# RFID_bmd200.net
KiCad netlist of a schematic drawn in EAGLE
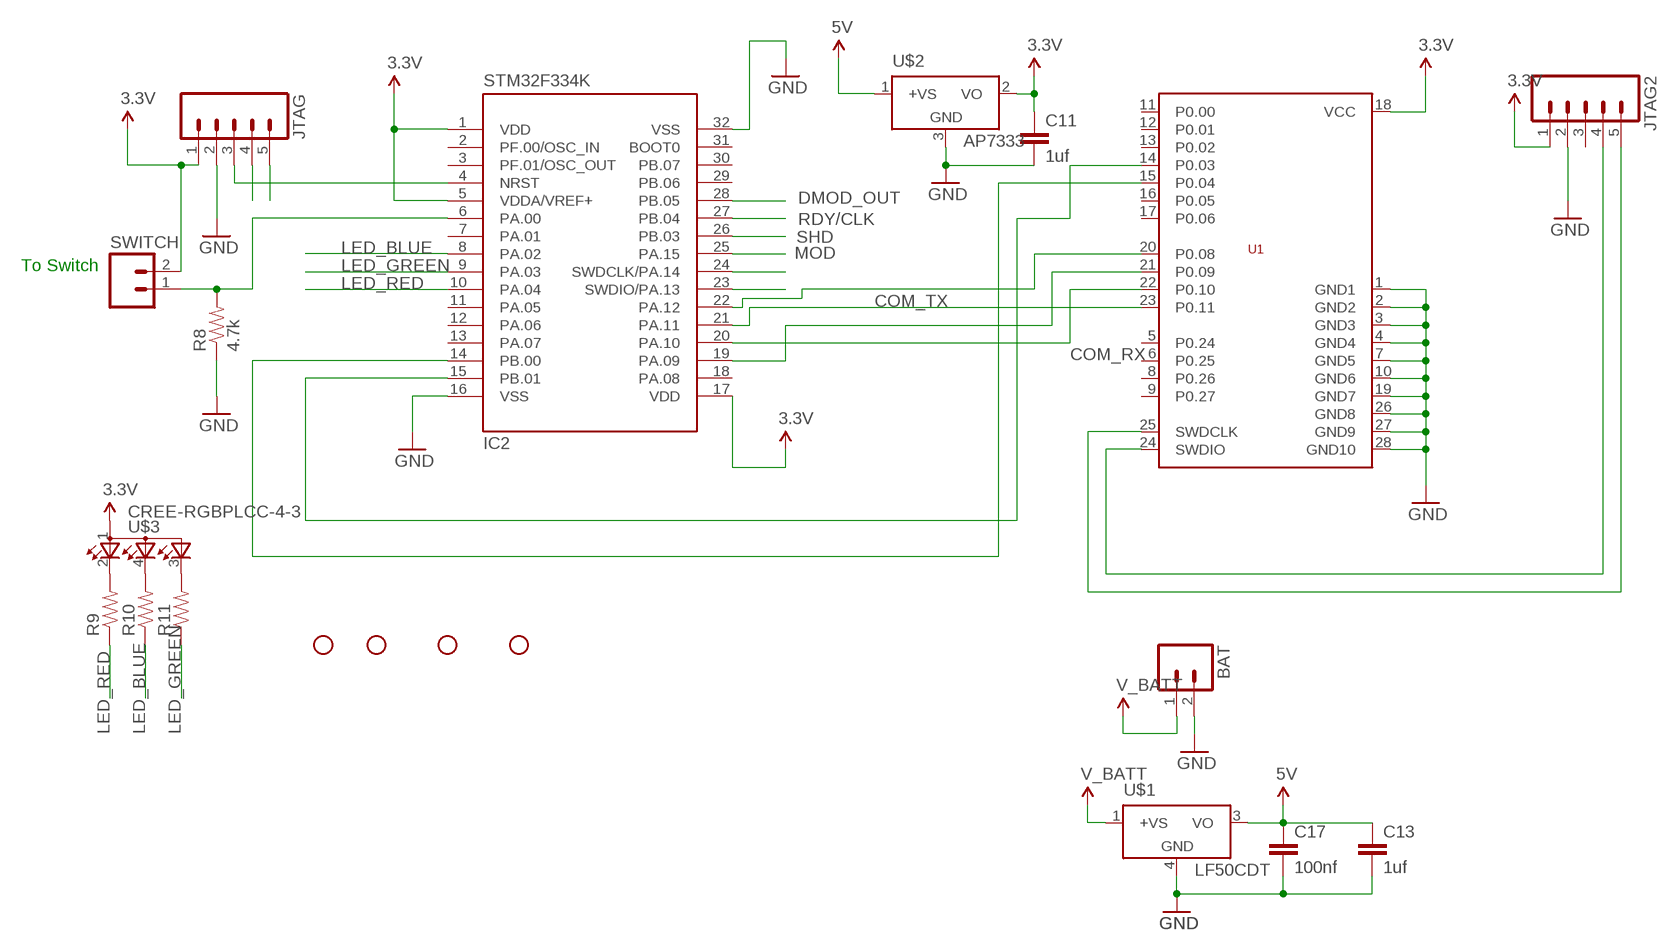
[diagram p0: schematic, sheet 1]
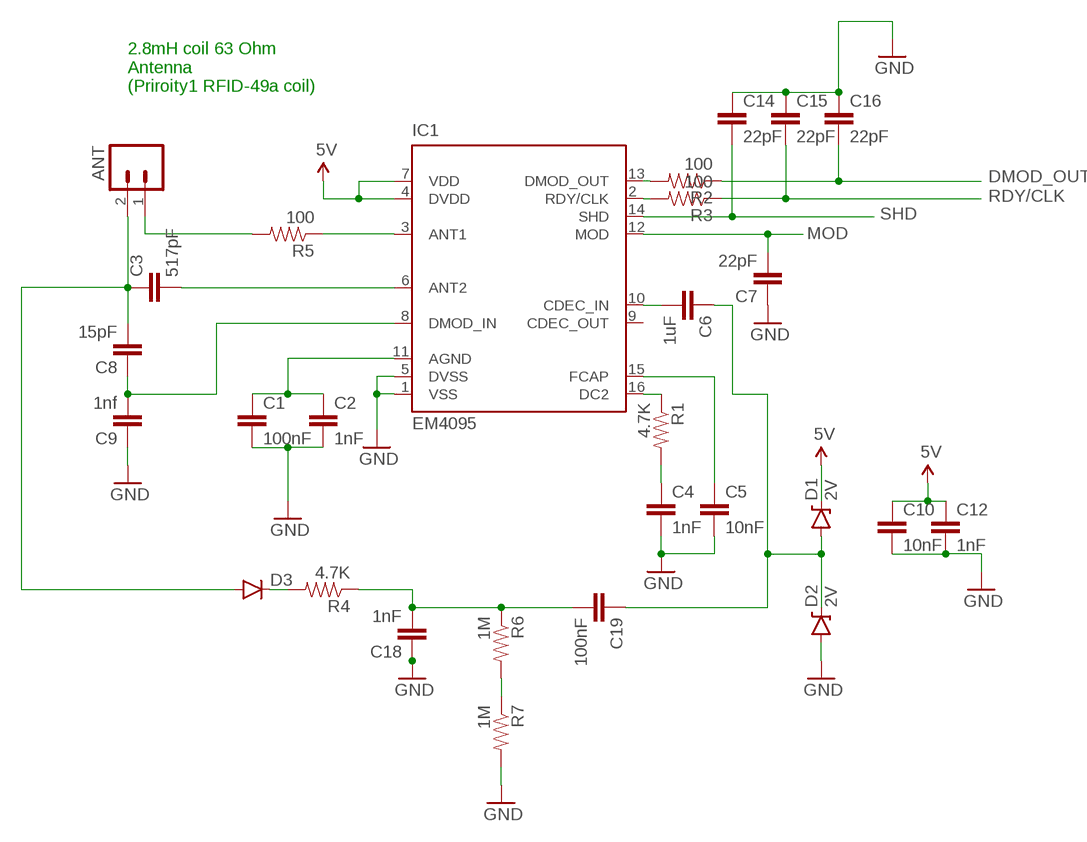
[diagram p1: schematic, sheet 2]

(export (version "E")
  (design (tool "Eeschema 10.0.6"))
  (components
    (comp (ref "BAT")
      (value "M02PTH")
      (footprint "eagle-import:1X02")
      (libsource (lib "eagle-import") (part "M02PTH"))
    )
    (comp (ref "C11")
      (value "1uf")
      (footprint "eagle-import:0805")
      (libsource (lib "eagle-import") (part "CAP0805"))
    )
    (comp (ref "C13")
      (value "1uf")
      (footprint "eagle-import:0805")
      (libsource (lib "eagle-import") (part "CAP0805"))
    )
    (comp (ref "C17")
      (value "100nf")
      (footprint "eagle-import:0805")
      (libsource (lib "eagle-import") (part "CAP0805"))
    )
    (comp (ref "IC2")
      (value "STM32F334K")
      (footprint "eagle-import:LQFP-32")
      (libsource (lib "eagle-import") (part "STM32F334K"))
    )
    (comp (ref "JTAG")
      (value "M05PTH")
      (footprint "eagle-import:1X05")
      (libsource (lib "eagle-import") (part "M05PTH"))
    )
    (comp (ref "JTAG2")
      (value "M05PTH")
      (footprint "eagle-import:1X05")
      (libsource (lib "eagle-import") (part "M05PTH"))
    )
    (comp (ref "R8")
      (value "4.7k")
      (footprint "eagle-import:0805")
      (libsource (lib "eagle-import") (part "RESISTOR0805-RES"))
    )
    (comp (ref "R9")
      (value "RESISTOR0805-RES")
      (footprint "eagle-import:0805")
      (libsource (lib "eagle-import") (part "RESISTOR0805-RES"))
    )
    (comp (ref "R10")
      (value "RESISTOR0805-RES")
      (footprint "eagle-import:0805")
      (libsource (lib "eagle-import") (part "RESISTOR0805-RES"))
    )
    (comp (ref "R11")
      (value "RESISTOR0805-RES")
      (footprint "eagle-import:0805")
      (libsource (lib "eagle-import") (part "RESISTOR0805-RES"))
    )
    (comp (ref "STANDOFF1")
      (value "STAND-OFF")
      (footprint "eagle-import:STAND-OFF")
      (libsource (lib "eagle-import") (part "STAND-OFF"))
    )
    (comp (ref "STANDOFF2")
      (value "STAND-OFF")
      (footprint "eagle-import:STAND-OFF")
      (libsource (lib "eagle-import") (part "STAND-OFF"))
    )
    (comp (ref "STANDOFF3")
      (value "STAND-OFF")
      (footprint "eagle-import:STAND-OFF")
      (libsource (lib "eagle-import") (part "STAND-OFF"))
    )
    (comp (ref "STANDOFF4")
      (value "STAND-OFF")
      (footprint "eagle-import:STAND-OFF")
      (libsource (lib "eagle-import") (part "STAND-OFF"))
    )
    (comp (ref "SWITCH")
      (value "M02PTH")
      (footprint "eagle-import:1X02")
      (libsource (lib "eagle-import") (part "M02PTH"))
    )
    (comp (ref "U$1")
      (value "LF50CDT")
      (footprint "eagle-import:DPACK_3")
      (libsource (lib "eagle-import") (part "LF50CDT"))
    )
    (comp (ref "U$2")
      (value "AP7333")
      (footprint "eagle-import:SOT23-3")
      (libsource (lib "eagle-import") (part "AP7333"))
    )
    (comp (ref "U$3")
      (value "CREE-RGBPLCC-4-3")
      (footprint "eagle-import:P-LCC-4-3")
      (libsource (lib "eagle-import") (part "CREE-RGBPLCC-4-3"))
    )
    (comp (ref "U1")
      (value "BMD-200")
      (footprint "eagle-import:BMD-200")
      (libsource (lib "eagle-import") (part "BMD-200"))
    )
    (comp (ref "ANT")
      (value "M02PTH")
      (footprint "eagle-import:1X02")
      (libsource (lib "eagle-import") (part "M02PTH"))
    )
    (comp (ref "C1")
      (value "100nF")
      (footprint "eagle-import:0805")
      (libsource (lib "eagle-import") (part "CAP0805"))
    )
    (comp (ref "C2")
      (value "1nF")
      (footprint "eagle-import:0805")
      (libsource (lib "eagle-import") (part "CAP0805"))
    )
    (comp (ref "C3")
      (value "517pF")
      (footprint "eagle-import:0805")
      (libsource (lib "eagle-import") (part "CAP0805"))
    )
    (comp (ref "C4")
      (value "1nF")
      (footprint "eagle-import:0805")
      (libsource (lib "eagle-import") (part "CAP0805"))
    )
    (comp (ref "C5")
      (value "10nF")
      (footprint "eagle-import:0805")
      (libsource (lib "eagle-import") (part "CAP0805"))
    )
    (comp (ref "C6")
      (value "1uF")
      (footprint "eagle-import:0805")
      (libsource (lib "eagle-import") (part "CAP0805"))
    )
    (comp (ref "C7")
      (value "22pF")
      (footprint "eagle-import:0805")
      (libsource (lib "eagle-import") (part "CAP0805"))
    )
    (comp (ref "C8")
      (value "15pF")
      (footprint "eagle-import:0805")
      (libsource (lib "eagle-import") (part "CAP0805"))
    )
    (comp (ref "C9")
      (value "1nf")
      (footprint "eagle-import:0805")
      (libsource (lib "eagle-import") (part "CAP0805"))
    )
    (comp (ref "C10")
      (value "10nF")
      (footprint "eagle-import:0805")
      (libsource (lib "eagle-import") (part "CAP0805"))
    )
    (comp (ref "C12")
      (value "1nF")
      (footprint "eagle-import:0805")
      (libsource (lib "eagle-import") (part "CAP0805"))
    )
    (comp (ref "C14")
      (value "22pF")
      (footprint "eagle-import:0805")
      (libsource (lib "eagle-import") (part "CAP0805"))
    )
    (comp (ref "C15")
      (value "22pF")
      (footprint "eagle-import:0805")
      (libsource (lib "eagle-import") (part "CAP0805"))
    )
    (comp (ref "C16")
      (value "22pF")
      (footprint "eagle-import:0805")
      (libsource (lib "eagle-import") (part "CAP0805"))
    )
    (comp (ref "C18")
      (value "1nF")
      (footprint "eagle-import:0805")
      (libsource (lib "eagle-import") (part "CAP0805"))
    )
    (comp (ref "C19")
      (value "100nF")
      (footprint "eagle-import:C1812")
      (libsource (lib "eagle-import") (part "CAP"))
    )
    (comp (ref "D1")
      (value "2V")
      (footprint "eagle-import:SOD-123")
      (libsource (lib "eagle-import") (part "DIODE-ZENER16V"))
    )
    (comp (ref "D2")
      (value "2V")
      (footprint "eagle-import:SOD-123")
      (libsource (lib "eagle-import") (part "DIODE-ZENER16V"))
    )
    (comp (ref "D3")
      (value "DIODESMF")
      (footprint "eagle-import:SMF")
      (libsource (lib "eagle-import") (part "DIODESMF"))
    )
    (comp (ref "IC1")
      (value "EM4095")
      (footprint "eagle-import:SO16")
      (libsource (lib "eagle-import") (part "EM4095"))
    )
    (comp (ref "R1")
      (value "4.7K")
      (footprint "eagle-import:0805")
      (libsource (lib "eagle-import") (part "RESISTOR0805-RES"))
    )
    (comp (ref "R2")
      (value "100")
      (footprint "eagle-import:0805")
      (libsource (lib "eagle-import") (part "RESISTOR0805-RES"))
    )
    (comp (ref "R3")
      (value "100")
      (footprint "eagle-import:0805")
      (libsource (lib "eagle-import") (part "RESISTOR0805-RES"))
    )
    (comp (ref "R4")
      (value "4.7K")
      (footprint "eagle-import:0805")
      (libsource (lib "eagle-import") (part "RESISTOR0805-RES"))
    )
    (comp (ref "R5")
      (value "100")
      (footprint "eagle-import:0805")
      (libsource (lib "eagle-import") (part "RESISTOR0805-RES"))
    )
    (comp (ref "R6")
      (value "1M")
      (footprint "eagle-import:0805")
      (libsource (lib "eagle-import") (part "RESISTOR0805-RES"))
    )
    (comp (ref "R7")
      (value "1M")
      (footprint "eagle-import:0805")
      (libsource (lib "eagle-import") (part "RESISTOR0805-RES"))
    )
  )
  (nets
    (net (code "1") (name "3.3V") (class "Default")
      (node (ref "C11") (pin "1") (pinfunction "1_1") (pintype "passive"))
      (node (ref "IC2") (pin "1") (pinfunction "VDD_1") (pintype "power_in"))
      (node (ref "IC2") (pin "17") (pinfunction "VDD_17") (pintype "power_in"))
      (node (ref "IC2") (pin "5") (pinfunction "VDDA/VREF+_5") (pintype "power_in"))
      (node (ref "JTAG") (pin "1") (pinfunction "1_1") (pintype "passive"))
      (node (ref "JTAG2") (pin "1") (pinfunction "1_1") (pintype "passive"))
      (node (ref "SWITCH") (pin "2") (pinfunction "2_2") (pintype "passive"))
      (node (ref "U$2") (pin "2") (pinfunction "VO_2") (pintype "input"))
      (node (ref "U$3") (pin "1") (pinfunction "A2_1") (pintype "passive"))
      (node (ref "U1") (pin "18") (pinfunction "VCC_18") (pintype "bidirectional"))
    )
    (net (code "2") (name "5V") (class "Default")
      (node (ref "C10") (pin "1") (pinfunction "1_1") (pintype "passive"))
      (node (ref "C12") (pin "1") (pinfunction "1_1") (pintype "passive"))
      (node (ref "C13") (pin "1") (pinfunction "1_1") (pintype "passive"))
      (node (ref "C17") (pin "1") (pinfunction "1_1") (pintype "passive"))
      (node (ref "D1") (pin "C") (pinfunction "C_C") (pintype "passive"))
      (node (ref "IC1") (pin "4") (pinfunction "DVDD_4") (pintype "power_in"))
      (node (ref "IC1") (pin "7") (pinfunction "VDD_7") (pintype "power_in"))
      (node (ref "U$1") (pin "3") (pinfunction "VO_3") (pintype "input"))
      (node (ref "U$2") (pin "1") (pinfunction "+VS_1") (pintype "input"))
    )
    (net (code "3") (name "COM_RX") (class "Default")
      (node (ref "IC2") (pin "20") (pinfunction "PA.10_20") (pintype "bidirectional"))
      (node (ref "U1") (pin "22") (pinfunction "P0.10_22") (pintype "bidirectional"))
    )
    (net (code "4") (name "COM_TX") (class "Default")
      (node (ref "IC2") (pin "19") (pinfunction "PA.09_19") (pintype "bidirectional"))
      (node (ref "U1") (pin "21") (pinfunction "P0.09_21") (pintype "bidirectional"))
    )
    (net (code "5") (name "DMOD_OUT") (class "Default")
      (node (ref "C16") (pin "2") (pinfunction "2_2") (pintype "passive"))
      (node (ref "IC2") (pin "28") (pinfunction "PB.05_28") (pintype "bidirectional"))
      (node (ref "R2") (pin "1") (pinfunction "1_1") (pintype "passive"))
    )
    (net (code "6") (name "GND") (class "Default")
      (node (ref "BAT") (pin "2") (pinfunction "2_2") (pintype "passive"))
      (node (ref "C1") (pin "2") (pinfunction "2_2") (pintype "passive"))
      (node (ref "C10") (pin "2") (pinfunction "2_2") (pintype "passive"))
      (node (ref "C11") (pin "2") (pinfunction "2_2") (pintype "passive"))
      (node (ref "C12") (pin "2") (pinfunction "2_2") (pintype "passive"))
      (node (ref "C13") (pin "2") (pinfunction "2_2") (pintype "passive"))
      (node (ref "C14") (pin "1") (pinfunction "1_1") (pintype "passive"))
      (node (ref "C15") (pin "1") (pinfunction "1_1") (pintype "passive"))
      (node (ref "C16") (pin "1") (pinfunction "1_1") (pintype "passive"))
      (node (ref "C17") (pin "2") (pinfunction "2_2") (pintype "passive"))
      (node (ref "C18") (pin "1") (pinfunction "1_1") (pintype "passive"))
      (node (ref "C2") (pin "2") (pinfunction "2_2") (pintype "passive"))
      (node (ref "C4") (pin "2") (pinfunction "2_2") (pintype "passive"))
      (node (ref "C5") (pin "2") (pinfunction "2_2") (pintype "passive"))
      (node (ref "C7") (pin "1") (pinfunction "1_1") (pintype "passive"))
      (node (ref "C9") (pin "1") (pinfunction "1_1") (pintype "passive"))
      (node (ref "D2") (pin "A") (pinfunction "A_A") (pintype "passive"))
      (node (ref "IC1") (pin "1") (pinfunction "VSS_1") (pintype "power_in"))
      (node (ref "IC1") (pin "5") (pinfunction "DVSS_5") (pintype "power_in"))
      (node (ref "IC2") (pin "16") (pinfunction "VSS_16") (pintype "power_in"))
      (node (ref "IC2") (pin "32") (pinfunction "VSS_32") (pintype "power_in"))
      (node (ref "JTAG") (pin "2") (pinfunction "2_2") (pintype "passive"))
      (node (ref "JTAG2") (pin "2") (pinfunction "2_2") (pintype "passive"))
      (node (ref "R7") (pin "2") (pinfunction "2_2") (pintype "passive"))
      (node (ref "R8") (pin "1") (pinfunction "1_1") (pintype "passive"))
      (node (ref "U$1") (pin "4") (pinfunction "GND_4") (pintype "power_in"))
      (node (ref "U$2") (pin "3") (pinfunction "GND_3") (pintype "power_in"))
      (node (ref "U1") (pin "1") (pinfunction "GND1_1") (pintype "bidirectional"))
      (node (ref "U1") (pin "10") (pinfunction "GND6_10") (pintype "bidirectional"))
      (node (ref "U1") (pin "19") (pinfunction "GND7_19") (pintype "bidirectional"))
      (node (ref "U1") (pin "2") (pinfunction "GND2_2") (pintype "bidirectional"))
      (node (ref "U1") (pin "26") (pinfunction "GND8_26") (pintype "bidirectional"))
      (node (ref "U1") (pin "27") (pinfunction "GND9_27") (pintype "bidirectional"))
      (node (ref "U1") (pin "28") (pinfunction "GND10_28") (pintype "bidirectional"))
      (node (ref "U1") (pin "3") (pinfunction "GND3_3") (pintype "bidirectional"))
      (node (ref "U1") (pin "4") (pinfunction "GND4_4") (pintype "bidirectional"))
      (node (ref "U1") (pin "7") (pinfunction "GND5_7") (pintype "bidirectional"))
    )
    (net (code "7") (name "LED_BLUE") (class "Default")
      (node (ref "IC2") (pin "8") (pinfunction "PA.02_8") (pintype "bidirectional"))
      (node (ref "R10") (pin "1") (pinfunction "1_1") (pintype "passive"))
    )
    (net (code "8") (name "LED_GREEN") (class "Default")
      (node (ref "IC2") (pin "9") (pinfunction "PA.03_9") (pintype "bidirectional"))
      (node (ref "R11") (pin "1") (pinfunction "1_1") (pintype "passive"))
    )
    (net (code "9") (name "LED_RED") (class "Default")
      (node (ref "IC2") (pin "10") (pinfunction "PA.04_10") (pintype "bidirectional"))
      (node (ref "R9") (pin "1") (pinfunction "1_1") (pintype "passive"))
    )
    (net (code "10") (name "MOD") (class "Default")
      (node (ref "C7") (pin "2") (pinfunction "2_2") (pintype "passive"))
      (node (ref "IC1") (pin "12") (pinfunction "MOD_12") (pintype "input"))
      (node (ref "IC2") (pin "25") (pinfunction "PA.15_25") (pintype "bidirectional"))
    )
    (net (code "11") (name "Net-(ANT-Pad1)") (class "Default")
      (node (ref "ANT") (pin "1") (pinfunction "1_1") (pintype "passive"))
      (node (ref "R5") (pin "2") (pinfunction "2_2") (pintype "passive"))
    )
    (net (code "12") (name "Net-(C4-Pad1)") (class "Default")
      (node (ref "C4") (pin "1") (pinfunction "1_1") (pintype "passive"))
      (node (ref "R1") (pin "2") (pinfunction "2_2") (pintype "passive"))
    )
    (net (code "13") (name "Net-(C18-Pad2)") (class "Default")
      (node (ref "C18") (pin "2") (pinfunction "2_2") (pintype "passive"))
      (node (ref "C19") (pin "2") (pinfunction "2_2") (pintype "passive"))
      (node (ref "R4") (pin "1") (pinfunction "1_1") (pintype "passive"))
      (node (ref "R6") (pin "1") (pinfunction "1_1") (pintype "passive"))
    )
    (net (code "14") (name "Net-(C19-Pad1)") (class "Default")
      (node (ref "C19") (pin "1") (pinfunction "1_1") (pintype "passive"))
      (node (ref "C6") (pin "1") (pinfunction "1_1") (pintype "passive"))
      (node (ref "D1") (pin "A") (pinfunction "A_A") (pintype "passive"))
      (node (ref "D2") (pin "C") (pinfunction "C_C") (pintype "passive"))
    )
    (net (code "15") (name "Net-(D3-A)") (class "Default")
      (node (ref "ANT") (pin "2") (pinfunction "2_2") (pintype "passive"))
      (node (ref "C3") (pin "1") (pinfunction "1_1") (pintype "passive"))
      (node (ref "C8") (pin "2") (pinfunction "2_2") (pintype "passive"))
      (node (ref "D3") (pin "P$2") (pinfunction "A_P$2") (pintype "passive"))
    )
    (net (code "16") (name "Net-(D3-C)") (class "Default")
      (node (ref "D3") (pin "P$1") (pinfunction "C_P$1") (pintype "passive"))
      (node (ref "R4") (pin "2") (pinfunction "2_2") (pintype "passive"))
    )
    (net (code "17") (name "Net-(IC1-AGND)") (class "Default")
      (node (ref "C1") (pin "1") (pinfunction "1_1") (pintype "passive"))
      (node (ref "C2") (pin "1") (pinfunction "1_1") (pintype "passive"))
      (node (ref "IC1") (pin "11") (pinfunction "AGND_11") (pintype "power_in"))
    )
    (net (code "18") (name "Net-(IC1-ANT1)") (class "Default")
      (node (ref "IC1") (pin "3") (pinfunction "ANT1_3") (pintype "passive"))
      (node (ref "R5") (pin "1") (pinfunction "1_1") (pintype "passive"))
    )
    (net (code "19") (name "Net-(IC1-ANT2)") (class "Default")
      (node (ref "C3") (pin "2") (pinfunction "2_2") (pintype "passive"))
      (node (ref "IC1") (pin "6") (pinfunction "ANT2_6") (pintype "passive"))
    )
    (net (code "20") (name "Net-(IC1-CDEC_IN)") (class "Default")
      (node (ref "C6") (pin "2") (pinfunction "2_2") (pintype "passive"))
      (node (ref "IC1") (pin "10") (pinfunction "CDEC_IN_10") (pintype "input"))
    )
    (net (code "21") (name "Net-(IC1-DC2)") (class "Default")
      (node (ref "IC1") (pin "16") (pinfunction "DC2_16") (pintype "passive"))
      (node (ref "R1") (pin "1") (pinfunction "1_1") (pintype "passive"))
    )
    (net (code "22") (name "Net-(IC1-DMOD_IN)") (class "Default")
      (node (ref "C8") (pin "1") (pinfunction "1_1") (pintype "passive"))
      (node (ref "C9") (pin "2") (pinfunction "2_2") (pintype "passive"))
      (node (ref "IC1") (pin "8") (pinfunction "DMOD_IN_8") (pintype "input"))
    )
    (net (code "23") (name "Net-(IC1-DMOD_OUT)") (class "Default")
      (node (ref "IC1") (pin "13") (pinfunction "DMOD_OUT_13") (pintype "output"))
      (node (ref "R2") (pin "2") (pinfunction "2_2") (pintype "passive"))
    )
    (net (code "24") (name "Net-(IC1-FCAP)") (class "Default")
      (node (ref "C5") (pin "1") (pinfunction "1_1") (pintype "passive"))
      (node (ref "IC1") (pin "15") (pinfunction "FCAP_15") (pintype "passive"))
    )
    (net (code "25") (name "Net-(IC1-RDY{slash}CLK)") (class "Default")
      (node (ref "IC1") (pin "2") (pinfunction "RDY/CLK_2") (pintype "output"))
      (node (ref "R3") (pin "2") (pinfunction "2_2") (pintype "passive"))
    )
    (net (code "26") (name "Net-(IC2-NRST)") (class "Default")
      (node (ref "IC2") (pin "4") (pinfunction "NRST_4") (pintype "bidirectional"))
      (node (ref "JTAG") (pin "3") (pinfunction "3_3") (pintype "passive"))
    )
    (net (code "27") (name "Net-(IC2-PA.00)") (class "Default")
      (node (ref "IC2") (pin "6") (pinfunction "PA.00_6") (pintype "bidirectional"))
      (node (ref "R8") (pin "2") (pinfunction "2_2") (pintype "passive"))
      (node (ref "SWITCH") (pin "1") (pinfunction "1_1") (pintype "passive"))
    )
    (net (code "28") (name "Net-(IC2-PA.11)") (class "Default")
      (node (ref "IC2") (pin "21") (pinfunction "PA.11_21") (pintype "bidirectional"))
      (node (ref "U1") (pin "23") (pinfunction "P0.11_23") (pintype "bidirectional"))
    )
    (net (code "29") (name "Net-(IC2-PA.12)") (class "Default")
      (node (ref "IC2") (pin "22") (pinfunction "PA.12_22") (pintype "bidirectional"))
      (node (ref "U1") (pin "20") (pinfunction "P0.08_20") (pintype "bidirectional"))
    )
    (net (code "30") (name "Net-(IC2-PB.00)") (class "Default")
      (node (ref "IC2") (pin "14") (pinfunction "PB.00_14") (pintype "bidirectional"))
      (node (ref "U1") (pin "15") (pinfunction "P0.04_15") (pintype "bidirectional"))
    )
    (net (code "31") (name "Net-(IC2-PB.01)") (class "Default")
      (node (ref "IC2") (pin "15") (pinfunction "PB.01_15") (pintype "bidirectional"))
      (node (ref "U1") (pin "14") (pinfunction "P0.03_14") (pintype "bidirectional"))
    )
    (net (code "32") (name "Net-(R6-Pad2)") (class "Default")
      (node (ref "R6") (pin "2") (pinfunction "2_2") (pintype "passive"))
      (node (ref "R7") (pin "1") (pinfunction "1_1") (pintype "passive"))
    )
    (net (code "33") (name "Net-(U$3-CBLUE)") (class "Default")
      (node (ref "R10") (pin "2") (pinfunction "2_2") (pintype "passive"))
      (node (ref "U$3") (pin "4") (pinfunction "CBLUE_4") (pintype "passive"))
    )
    (net (code "34") (name "Net-(U$3-CGREEN)") (class "Default")
      (node (ref "R11") (pin "2") (pinfunction "2_2") (pintype "passive"))
      (node (ref "U$3") (pin "3") (pinfunction "CGREEN_3") (pintype "passive"))
    )
    (net (code "35") (name "Net-(U$3-CRED)") (class "Default")
      (node (ref "R9") (pin "2") (pinfunction "2_2") (pintype "passive"))
      (node (ref "U$3") (pin "2") (pinfunction "CRED_2") (pintype "passive"))
    )
    (net (code "36") (name "Net-(U1-SWDCLK)") (class "Default")
      (node (ref "JTAG2") (pin "5") (pinfunction "5_5") (pintype "passive"))
      (node (ref "U1") (pin "25") (pinfunction "SWDCLK_25") (pintype "bidirectional"))
    )
    (net (code "37") (name "Net-(U1-SWDIO)") (class "Default")
      (node (ref "JTAG2") (pin "4") (pinfunction "4_4") (pintype "passive"))
      (node (ref "U1") (pin "24") (pinfunction "SWDIO_24") (pintype "bidirectional"))
    )
    (net (code "38") (name "RDY{slash}CLK") (class "Default")
      (node (ref "C15") (pin "2") (pinfunction "2_2") (pintype "passive"))
      (node (ref "IC2") (pin "27") (pinfunction "PB.04_27") (pintype "bidirectional"))
      (node (ref "R3") (pin "1") (pinfunction "1_1") (pintype "passive"))
    )
    (net (code "39") (name "SHD") (class "Default")
      (node (ref "C14") (pin "2") (pinfunction "2_2") (pintype "passive"))
      (node (ref "IC1") (pin "14") (pinfunction "SHD_14") (pintype "input"))
      (node (ref "IC2") (pin "26") (pinfunction "PB.03_26") (pintype "bidirectional"))
    )
    (net (code "40") (name "STM_SWDCLK") (class "Default")
      (node (ref "IC2") (pin "24") (pinfunction "SWDCLK/PA.14_24") (pintype "bidirectional"))
      (node (ref "JTAG") (pin "5") (pinfunction "5_5") (pintype "passive"))
    )
    (net (code "41") (name "STM_SWDIO") (class "Default")
      (node (ref "IC2") (pin "23") (pinfunction "SWDIO/PA.13_23") (pintype "bidirectional"))
      (node (ref "JTAG") (pin "4") (pinfunction "4_4") (pintype "passive"))
    )
    (net (code "42") (name "V_BATT") (class "Default")
      (node (ref "BAT") (pin "1") (pinfunction "1_1") (pintype "passive"))
      (node (ref "U$1") (pin "1") (pinfunction "+VS_1") (pintype "input"))
    )
    (net (code "43") (name "unconnected-(IC1-CDEC_OUT-Pad9)") (class "Default")
      (node (ref "IC1") (pin "9") (pinfunction "CDEC_OUT_9") (pintype "output"))
    )
    (net (code "44") (name "unconnected-(IC2-BOOT0-Pad31)") (class "Default")
      (node (ref "IC2") (pin "31") (pinfunction "BOOT0_31") (pintype "bidirectional"))
    )
    (net (code "45") (name "unconnected-(IC2-PA.01-Pad7)") (class "Default")
      (node (ref "IC2") (pin "7") (pinfunction "PA.01_7") (pintype "bidirectional"))
    )
    (net (code "46") (name "unconnected-(IC2-PA.05-Pad11)") (class "Default")
      (node (ref "IC2") (pin "11") (pinfunction "PA.05_11") (pintype "bidirectional"))
    )
    (net (code "47") (name "unconnected-(IC2-PA.06-Pad12)") (class "Default")
      (node (ref "IC2") (pin "12") (pinfunction "PA.06_12") (pintype "bidirectional"))
    )
    (net (code "48") (name "unconnected-(IC2-PA.07-Pad13)") (class "Default")
      (node (ref "IC2") (pin "13") (pinfunction "PA.07_13") (pintype "bidirectional"))
    )
    (net (code "49") (name "unconnected-(IC2-PA.08-Pad18)") (class "Default")
      (node (ref "IC2") (pin "18") (pinfunction "PA.08_18") (pintype "bidirectional"))
    )
    (net (code "50") (name "unconnected-(IC2-PB.06-Pad29)") (class "Default")
      (node (ref "IC2") (pin "29") (pinfunction "PB.06_29") (pintype "bidirectional"))
    )
    (net (code "51") (name "unconnected-(IC2-PB.07-Pad30)") (class "Default")
      (node (ref "IC2") (pin "30") (pinfunction "PB.07_30") (pintype "bidirectional"))
    )
    (net (code "52") (name "unconnected-(IC2-PF.00{slash}OSC_IN-Pad2)") (class "Default")
      (node (ref "IC2") (pin "2") (pinfunction "PF.00/OSC_IN_2") (pintype "bidirectional"))
    )
    (net (code "53") (name "unconnected-(IC2-PF.01{slash}OSC_OUT-Pad3)") (class "Default")
      (node (ref "IC2") (pin "3") (pinfunction "PF.01/OSC_OUT_3") (pintype "bidirectional"))
    )
    (net (code "54") (name "unconnected-(JTAG2-Pad3)") (class "Default")
      (node (ref "JTAG2") (pin "3") (pinfunction "3_3") (pintype "passive"))
    )
    (net (code "55") (name "unconnected-(U1-P0.00-Pad11)") (class "Default")
      (node (ref "U1") (pin "11") (pinfunction "P0.00_11") (pintype "bidirectional"))
    )
    (net (code "56") (name "unconnected-(U1-P0.01-Pad12)") (class "Default")
      (node (ref "U1") (pin "12") (pinfunction "P0.01_12") (pintype "bidirectional"))
    )
    (net (code "57") (name "unconnected-(U1-P0.02-Pad13)") (class "Default")
      (node (ref "U1") (pin "13") (pinfunction "P0.02_13") (pintype "bidirectional"))
    )
    (net (code "58") (name "unconnected-(U1-P0.05-Pad16)") (class "Default")
      (node (ref "U1") (pin "16") (pinfunction "P0.05_16") (pintype "bidirectional"))
    )
    (net (code "59") (name "unconnected-(U1-P0.06-Pad17)") (class "Default")
      (node (ref "U1") (pin "17") (pinfunction "P0.06_17") (pintype "bidirectional"))
    )
    (net (code "60") (name "unconnected-(U1-P0.24-Pad5)") (class "Default")
      (node (ref "U1") (pin "5") (pinfunction "P0.24_5") (pintype "bidirectional"))
    )
    (net (code "61") (name "unconnected-(U1-P0.25-Pad6)") (class "Default")
      (node (ref "U1") (pin "6") (pinfunction "P0.25_6") (pintype "bidirectional"))
    )
    (net (code "62") (name "unconnected-(U1-P0.26-Pad8)") (class "Default")
      (node (ref "U1") (pin "8") (pinfunction "P0.26_8") (pintype "bidirectional"))
    )
    (net (code "63") (name "unconnected-(U1-P0.27-Pad9)") (class "Default")
      (node (ref "U1") (pin "9") (pinfunction "P0.27_9") (pintype "bidirectional"))
    )
  )
)
